# 5_POWER.net
KiCad netlist of a schematic drawn in Altium Designer
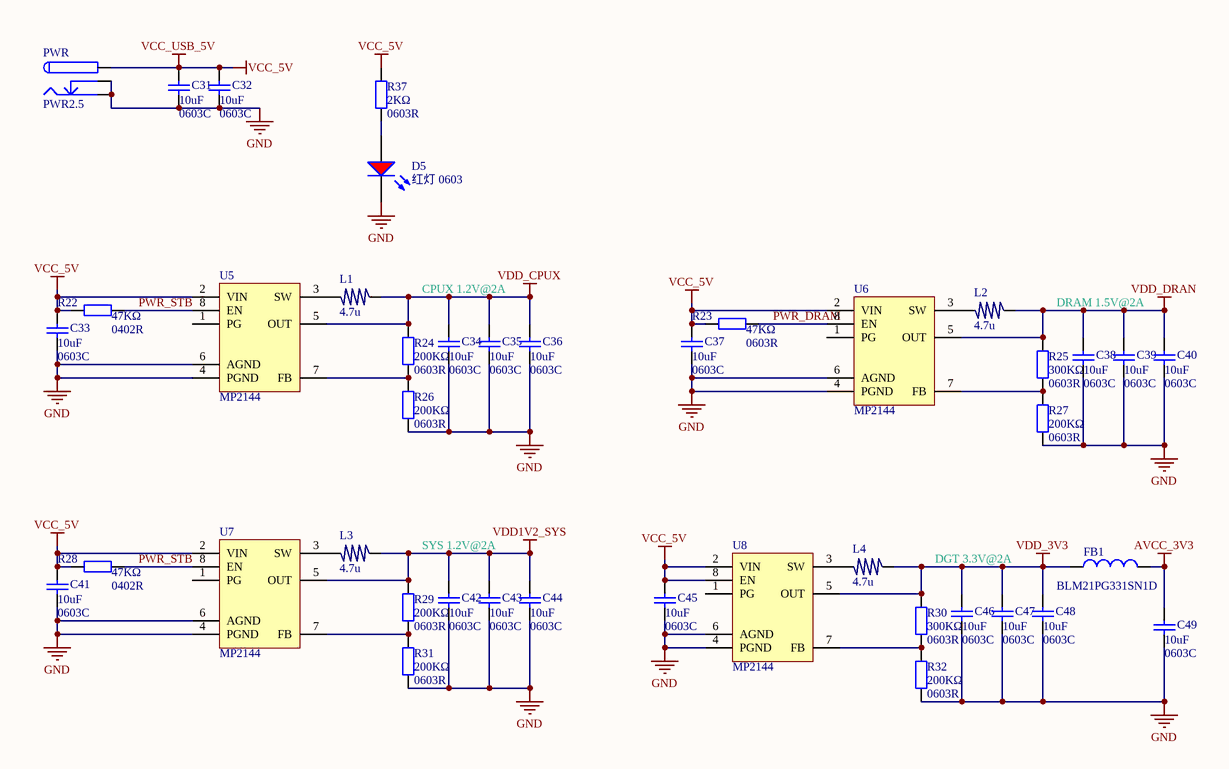
[diagram p0: 5_POWER.SchDoc]

(export (version "E")
  (design (tool "Eeschema 10.0.6"))
  (components
    (comp (ref "C31")
      (value "10uF")
      (footprint "0603_C")
      (description "贴片电容")
      (fields (field (name "PACKAGE") "0603C"))
      (libsource (lib "Miscellaneous Devices LC") (part "0603 1uF (105) 10% 50V"))
    )
    (comp (ref "C32")
      (value "10uF")
      (footprint "0603_C")
      (description "贴片电容")
      (fields (field (name "PACKAGE") "0603C"))
      (libsource (lib "Miscellaneous Devices LC") (part "0603 1uF (105) 10% 50V"))
    )
    (comp (ref "C33")
      (value "10uF")
      (footprint "0603_C")
      (description "贴片电容")
      (fields (field (name "PACKAGE") "0603C"))
      (libsource (lib "Miscellaneous Devices LC") (part "0603 1uF (105) 10% 50V"))
    )
    (comp (ref "C34")
      (value "10uF")
      (footprint "0603_C")
      (description "贴片电容")
      (fields (field (name "PACKAGE") "0603C"))
      (libsource (lib "Miscellaneous Devices LC") (part "0603 1uF (105) 10% 50V"))
    )
    (comp (ref "C35")
      (value "10uF")
      (footprint "0603_C")
      (description "贴片电容")
      (fields (field (name "PACKAGE") "0603C"))
      (libsource (lib "Miscellaneous Devices LC") (part "0603 1uF (105) 10% 50V"))
    )
    (comp (ref "C36")
      (value "10uF")
      (footprint "0603_C")
      (description "贴片电容")
      (fields (field (name "PACKAGE") "0603C"))
      (libsource (lib "Miscellaneous Devices LC") (part "0603 1uF (105) 10% 50V"))
    )
    (comp (ref "C37")
      (value "10uF")
      (footprint "0603_C")
      (description "贴片电容")
      (fields (field (name "PACKAGE") "0603C"))
      (libsource (lib "Miscellaneous Devices LC") (part "0603 1uF (105) 10% 50V"))
    )
    (comp (ref "C38")
      (value "10uF")
      (footprint "0603_C")
      (description "贴片电容")
      (fields (field (name "PACKAGE") "0603C"))
      (libsource (lib "Miscellaneous Devices LC") (part "0603 1uF (105) 10% 50V"))
    )
    (comp (ref "C39")
      (value "10uF")
      (footprint "0603_C")
      (description "贴片电容")
      (fields (field (name "PACKAGE") "0603C"))
      (libsource (lib "Miscellaneous Devices LC") (part "0603 1uF (105) 10% 50V"))
    )
    (comp (ref "C40")
      (value "10uF")
      (footprint "0603_C")
      (description "贴片电容")
      (fields (field (name "PACKAGE") "0603C"))
      (libsource (lib "Miscellaneous Devices LC") (part "0603 1uF (105) 10% 50V"))
    )
    (comp (ref "C41")
      (value "10uF")
      (footprint "0603_C")
      (description "贴片电容")
      (fields (field (name "PACKAGE") "0603C"))
      (libsource (lib "Miscellaneous Devices LC") (part "0603 1uF (105) 10% 50V"))
    )
    (comp (ref "C42")
      (value "10uF")
      (footprint "0603_C")
      (description "贴片电容")
      (fields (field (name "PACKAGE") "0603C"))
      (libsource (lib "Miscellaneous Devices LC") (part "0603 1uF (105) 10% 50V"))
    )
    (comp (ref "C43")
      (value "10uF")
      (footprint "0603_C")
      (description "贴片电容")
      (fields (field (name "PACKAGE") "0603C"))
      (libsource (lib "Miscellaneous Devices LC") (part "0603 1uF (105) 10% 50V"))
    )
    (comp (ref "C44")
      (value "10uF")
      (footprint "0603_C")
      (description "贴片电容")
      (fields (field (name "PACKAGE") "0603C"))
      (libsource (lib "Miscellaneous Devices LC") (part "0603 1uF (105) 10% 50V"))
    )
    (comp (ref "C45")
      (value "10uF")
      (footprint "0603_C")
      (description "贴片电容")
      (fields (field (name "PACKAGE") "0603C"))
      (libsource (lib "Miscellaneous Devices LC") (part "0603 1uF (105) 10% 50V"))
    )
    (comp (ref "C46")
      (value "10uF")
      (footprint "0603_C")
      (description "贴片电容")
      (fields (field (name "PACKAGE") "0603C"))
      (libsource (lib "Miscellaneous Devices LC") (part "0603 1uF (105) 10% 50V"))
    )
    (comp (ref "C47")
      (value "10uF")
      (footprint "0603_C")
      (description "贴片电容")
      (fields (field (name "PACKAGE") "0603C"))
      (libsource (lib "Miscellaneous Devices LC") (part "0603 1uF (105) 10% 50V"))
    )
    (comp (ref "C48")
      (value "10uF")
      (footprint "0603_C")
      (description "贴片电容")
      (fields (field (name "PACKAGE") "0603C"))
      (libsource (lib "Miscellaneous Devices LC") (part "0603 1uF (105) 10% 50V"))
    )
    (comp (ref "C49")
      (value "10uF")
      (footprint "0603_C")
      (description "贴片电容")
      (fields (field (name "PACKAGE") "0603C"))
      (libsource (lib "Miscellaneous Devices LC") (part "0603 1uF (105) 10% 50V"))
    )
    (comp (ref "D5")
      (value "红灯 0603")
      (footprint "0603_LED_S1")
      (description "发光二极管")
      (libsource (lib "Miscellaneous Devices LC") (part "0603 红灯"))
    )
    (comp (ref "FB1")
      (value "BLM21PG331SN1D")
      (footprint "F0805")
      (description "磁珠")
      (libsource (lib "MAGNET_L") (part "FB"))
    )
    (comp (ref "L1")
      (value "4.7u")
      (footprint "CD43NP")
      (fields (field (name "Comment") "4R7_CD43"))
      (libsource (lib "MAGNET_L") (part "L"))
    )
    (comp (ref "L2")
      (value "4.7u")
      (footprint "CD43NP")
      (fields (field (name "Comment") "4R7_CD43"))
      (libsource (lib "MAGNET_L") (part "L"))
    )
    (comp (ref "L3")
      (value "4.7u")
      (footprint "CD43NP")
      (fields (field (name "Comment") "4R7_CD43"))
      (libsource (lib "MAGNET_L") (part "L"))
    )
    (comp (ref "L4")
      (value "4.7u")
      (footprint "CD43NP")
      (fields (field (name "Comment") "4R7_CD43"))
      (libsource (lib "MAGNET_L") (part "L"))
    )
    (comp (ref "PWR")
      (value "PWR2.5")
      (footprint "DC-PJ044A")
      (description "Low Voltage Power Supply Connector")
      (fields (field (name "PUBLISHER") "Altium Limited"))
      (libsource (lib "MAGNET_L") (part "PWR2.5"))
    )
    (comp (ref "R22")
      (value "47KΩ")
      (footprint "0402_R")
      (description "贴片电阻")
      (fields (field (name "PACKAGE") "0402R"))
      (libsource (lib "") (part "0402 1KΩ (1001) 1%_1"))
    )
    (comp (ref "R23")
      (value "47KΩ")
      (footprint "0603_R")
      (description "贴片电阻")
      (fields (field (name "PACKAGE") "0603R"))
      (libsource (lib "") (part "0402 1KΩ (1001) 1%_1"))
    )
    (comp (ref "R24")
      (value "200KΩ")
      (footprint "0603_R")
      (description "贴片电阻")
      (fields (field (name "PACKAGE") "0603R"))
      (libsource (lib "Miscellaneous Devices LC") (part "0402 1KΩ (1001) 1%"))
    )
    (comp (ref "R25")
      (value "300KΩ")
      (footprint "0603_R")
      (description "贴片电阻")
      (fields (field (name "PACKAGE") "0603R"))
      (libsource (lib "Miscellaneous Devices LC") (part "0402 1KΩ (1001) 1%"))
    )
    (comp (ref "R26")
      (value "200KΩ")
      (footprint "0603_R")
      (description "贴片电阻")
      (fields (field (name "PACKAGE") "0603R"))
      (libsource (lib "Miscellaneous Devices LC") (part "0402 1KΩ (1001) 1%"))
    )
    (comp (ref "R27")
      (value "200KΩ")
      (footprint "0603_R")
      (description "贴片电阻")
      (fields (field (name "PACKAGE") "0603R"))
      (libsource (lib "Miscellaneous Devices LC") (part "0402 1KΩ (1001) 1%"))
    )
    (comp (ref "R28")
      (value "47KΩ")
      (footprint "0402_R")
      (description "贴片电阻")
      (fields (field (name "PACKAGE") "0402R"))
      (libsource (lib "") (part "0402 1KΩ (1001) 1%_1"))
    )
    (comp (ref "R29")
      (value "200KΩ")
      (footprint "0603_R")
      (description "贴片电阻")
      (fields (field (name "PACKAGE") "0603R"))
      (libsource (lib "Miscellaneous Devices LC") (part "0402 1KΩ (1001) 1%"))
    )
    (comp (ref "R30")
      (value "300KΩ")
      (footprint "0603_R")
      (description "贴片电阻")
      (fields (field (name "PACKAGE") "0603R"))
      (libsource (lib "Miscellaneous Devices LC") (part "0402 1KΩ (1001) 1%"))
    )
    (comp (ref "R31")
      (value "200KΩ")
      (footprint "0603_R")
      (description "贴片电阻")
      (fields (field (name "PACKAGE") "0603R"))
      (libsource (lib "Miscellaneous Devices LC") (part "0402 1KΩ (1001) 1%"))
    )
    (comp (ref "R32")
      (value "200KΩ")
      (footprint "0603_R")
      (description "贴片电阻")
      (fields (field (name "PACKAGE") "0603R"))
      (libsource (lib "Miscellaneous Devices LC") (part "0402 1KΩ (1001) 1%"))
    )
    (comp (ref "R37")
      (value "2KΩ")
      (footprint "0603_R")
      (description "贴片电阻")
      (fields (field (name "PACKAGE") "0603R"))
      (libsource (lib "Miscellaneous Devices LC") (part "0402 1KΩ (1001) 1%"))
    )
    (comp (ref "U5") (value "MP2144") (footprint "SOT23-8") (libsource (lib "MAGNET_L") (part "MP2144")))
    (comp (ref "U6") (value "MP2144") (footprint "SOT23-8") (libsource (lib "MAGNET_L") (part "MP2144")))
    (comp (ref "U7") (value "MP2144") (footprint "SOT23-8") (libsource (lib "MAGNET_L") (part "MP2144")))
    (comp (ref "U8") (value "MP2144") (footprint "SOT23-8") (libsource (lib "MAGNET_L") (part "MP2144")))
  )
  (nets
    (net (code "1") (name "/PWR_DRAM") (class "Default")
      (node (ref "R23") (pin "2") (pinfunction "2_2") (pintype "passive"))
      (node (ref "U6") (pin "8") (pinfunction "EN_8") (pintype "passive"))
    )
    (net (code "2") (name "/PWR_STB") (class "Default")
      (node (ref "R22") (pin "2") (pinfunction "2_2") (pintype "passive"))
      (node (ref "R28") (pin "2") (pinfunction "2_2") (pintype "passive"))
      (node (ref "U5") (pin "8") (pinfunction "EN_8") (pintype "passive"))
      (node (ref "U7") (pin "8") (pinfunction "EN_8") (pintype "passive"))
    )
    (net (code "3") (name "AVCC_3V3") (class "Default")
      (node (ref "C49") (pin "2") (pinfunction "2_2") (pintype "passive"))
      (node (ref "FB1") (pin "2") (pinfunction "2_2") (pintype "passive"))
    )
    (net (code "4") (name "GND") (class "Default")
      (node (ref "C31") (pin "1") (pinfunction "1_1") (pintype "passive"))
      (node (ref "C32") (pin "1") (pinfunction "1_1") (pintype "passive"))
      (node (ref "C33") (pin "1") (pinfunction "1_1") (pintype "passive"))
      (node (ref "C34") (pin "1") (pinfunction "1_1") (pintype "passive"))
      (node (ref "C35") (pin "1") (pinfunction "1_1") (pintype "passive"))
      (node (ref "C36") (pin "1") (pinfunction "1_1") (pintype "passive"))
      (node (ref "C37") (pin "1") (pinfunction "1_1") (pintype "passive"))
      (node (ref "C38") (pin "1") (pinfunction "1_1") (pintype "passive"))
      (node (ref "C39") (pin "1") (pinfunction "1_1") (pintype "passive"))
      (node (ref "C40") (pin "1") (pinfunction "1_1") (pintype "passive"))
      (node (ref "C41") (pin "1") (pinfunction "1_1") (pintype "passive"))
      (node (ref "C42") (pin "1") (pinfunction "1_1") (pintype "passive"))
      (node (ref "C43") (pin "1") (pinfunction "1_1") (pintype "passive"))
      (node (ref "C44") (pin "1") (pinfunction "1_1") (pintype "passive"))
      (node (ref "C45") (pin "1") (pinfunction "1_1") (pintype "passive"))
      (node (ref "C46") (pin "1") (pinfunction "1_1") (pintype "passive"))
      (node (ref "C47") (pin "1") (pinfunction "1_1") (pintype "passive"))
      (node (ref "C48") (pin "1") (pinfunction "1_1") (pintype "passive"))
      (node (ref "C49") (pin "1") (pinfunction "1_1") (pintype "passive"))
      (node (ref "D5") (pin "K") (pinfunction "K_K") (pintype "passive"))
      (node (ref "PWR") (pin "2") (pinfunction "2_2") (pintype "passive"))
      (node (ref "PWR") (pin "3") (pinfunction "3_3") (pintype "passive"))
      (node (ref "R26") (pin "2") (pinfunction "2_2") (pintype "passive"))
      (node (ref "R27") (pin "2") (pinfunction "2_2") (pintype "passive"))
      (node (ref "R31") (pin "2") (pinfunction "2_2") (pintype "passive"))
      (node (ref "R32") (pin "2") (pinfunction "2_2") (pintype "passive"))
      (node (ref "U5") (pin "4") (pinfunction "PGND_4") (pintype "passive"))
      (node (ref "U5") (pin "6") (pinfunction "AGND_6") (pintype "passive"))
      (node (ref "U6") (pin "4") (pinfunction "PGND_4") (pintype "passive"))
      (node (ref "U6") (pin "6") (pinfunction "AGND_6") (pintype "passive"))
      (node (ref "U7") (pin "4") (pinfunction "PGND_4") (pintype "passive"))
      (node (ref "U7") (pin "6") (pinfunction "AGND_6") (pintype "passive"))
      (node (ref "U8") (pin "4") (pinfunction "PGND_4") (pintype "passive"))
      (node (ref "U8") (pin "6") (pinfunction "AGND_6") (pintype "passive"))
    )
    (net (code "5") (name "Net-(D5-PadA)") (class "Default")
      (node (ref "D5") (pin "A") (pinfunction "A_A") (pintype "passive"))
      (node (ref "R37") (pin "2") (pinfunction "2_2") (pintype "passive"))
    )
    (net (code "6") (name "Net-(U5-FB)") (class "Default")
      (node (ref "R24") (pin "2") (pinfunction "2_2") (pintype "passive"))
      (node (ref "R26") (pin "1") (pinfunction "1_1") (pintype "passive"))
      (node (ref "U5") (pin "7") (pinfunction "FB_7") (pintype "passive"))
    )
    (net (code "7") (name "Net-(U5-SW)") (class "Default")
      (node (ref "L1") (pin "2") (pintype "passive"))
      (node (ref "U5") (pin "3") (pinfunction "SW_3") (pintype "passive"))
    )
    (net (code "8") (name "Net-(U6-FB)") (class "Default")
      (node (ref "R25") (pin "2") (pinfunction "2_2") (pintype "passive"))
      (node (ref "R27") (pin "1") (pinfunction "1_1") (pintype "passive"))
      (node (ref "U6") (pin "7") (pinfunction "FB_7") (pintype "passive"))
    )
    (net (code "9") (name "Net-(U6-SW)") (class "Default")
      (node (ref "L2") (pin "2") (pintype "passive"))
      (node (ref "U6") (pin "3") (pinfunction "SW_3") (pintype "passive"))
    )
    (net (code "10") (name "Net-(U7-FB)") (class "Default")
      (node (ref "R29") (pin "2") (pinfunction "2_2") (pintype "passive"))
      (node (ref "R31") (pin "1") (pinfunction "1_1") (pintype "passive"))
      (node (ref "U7") (pin "7") (pinfunction "FB_7") (pintype "passive"))
    )
    (net (code "11") (name "Net-(U7-SW)") (class "Default")
      (node (ref "L3") (pin "2") (pintype "passive"))
      (node (ref "U7") (pin "3") (pinfunction "SW_3") (pintype "passive"))
    )
    (net (code "12") (name "Net-(U8-FB)") (class "Default")
      (node (ref "R30") (pin "2") (pinfunction "2_2") (pintype "passive"))
      (node (ref "R32") (pin "1") (pinfunction "1_1") (pintype "passive"))
      (node (ref "U8") (pin "7") (pinfunction "FB_7") (pintype "passive"))
    )
    (net (code "13") (name "Net-(U8-SW)") (class "Default")
      (node (ref "L4") (pin "2") (pintype "passive"))
      (node (ref "U8") (pin "3") (pinfunction "SW_3") (pintype "passive"))
    )
    (net (code "14") (name "VCC_5V") (class "Default")
      (node (ref "C31") (pin "2") (pinfunction "2_2") (pintype "passive"))
      (node (ref "C32") (pin "2") (pinfunction "2_2") (pintype "passive"))
      (node (ref "C33") (pin "2") (pinfunction "2_2") (pintype "passive"))
      (node (ref "C37") (pin "2") (pinfunction "2_2") (pintype "passive"))
      (node (ref "C41") (pin "2") (pinfunction "2_2") (pintype "passive"))
      (node (ref "C45") (pin "2") (pinfunction "2_2") (pintype "passive"))
      (node (ref "PWR") (pin "1") (pinfunction "1_1") (pintype "passive"))
      (node (ref "R22") (pin "1") (pinfunction "1_1") (pintype "passive"))
      (node (ref "R23") (pin "1") (pinfunction "1_1") (pintype "passive"))
      (node (ref "R28") (pin "1") (pinfunction "1_1") (pintype "passive"))
      (node (ref "R37") (pin "1") (pinfunction "1_1") (pintype "passive"))
      (node (ref "U5") (pin "2") (pinfunction "VIN_2") (pintype "passive"))
      (node (ref "U6") (pin "2") (pinfunction "VIN_2") (pintype "passive"))
      (node (ref "U7") (pin "2") (pinfunction "VIN_2") (pintype "passive"))
      (node (ref "U8") (pin "2") (pinfunction "VIN_2") (pintype "passive"))
      (node (ref "U8") (pin "8") (pinfunction "EN_8") (pintype "passive"))
    )
    (net (code "15") (name "VDD1V2_SYS") (class "Default")
      (node (ref "C42") (pin "2") (pinfunction "2_2") (pintype "passive"))
      (node (ref "C43") (pin "2") (pinfunction "2_2") (pintype "passive"))
      (node (ref "C44") (pin "2") (pinfunction "2_2") (pintype "passive"))
      (node (ref "L3") (pin "1") (pintype "passive"))
      (node (ref "R29") (pin "1") (pinfunction "1_1") (pintype "passive"))
      (node (ref "U7") (pin "5") (pinfunction "OUT_5") (pintype "passive"))
    )
    (net (code "16") (name "VDD_3V3") (class "Default")
      (node (ref "C46") (pin "2") (pinfunction "2_2") (pintype "passive"))
      (node (ref "C47") (pin "2") (pinfunction "2_2") (pintype "passive"))
      (node (ref "C48") (pin "2") (pinfunction "2_2") (pintype "passive"))
      (node (ref "FB1") (pin "1") (pinfunction "1_1") (pintype "passive"))
      (node (ref "L4") (pin "1") (pintype "passive"))
      (node (ref "R30") (pin "1") (pinfunction "1_1") (pintype "passive"))
      (node (ref "U8") (pin "5") (pinfunction "OUT_5") (pintype "passive"))
    )
    (net (code "17") (name "VDD_CPUX") (class "Default")
      (node (ref "C34") (pin "2") (pinfunction "2_2") (pintype "passive"))
      (node (ref "C35") (pin "2") (pinfunction "2_2") (pintype "passive"))
      (node (ref "C36") (pin "2") (pinfunction "2_2") (pintype "passive"))
      (node (ref "L1") (pin "1") (pintype "passive"))
      (node (ref "R24") (pin "1") (pinfunction "1_1") (pintype "passive"))
      (node (ref "U5") (pin "5") (pinfunction "OUT_5") (pintype "passive"))
    )
    (net (code "18") (name "VDD_DRAN") (class "Default")
      (node (ref "C38") (pin "2") (pinfunction "2_2") (pintype "passive"))
      (node (ref "C39") (pin "2") (pinfunction "2_2") (pintype "passive"))
      (node (ref "C40") (pin "2") (pinfunction "2_2") (pintype "passive"))
      (node (ref "L2") (pin "1") (pintype "passive"))
      (node (ref "R25") (pin "1") (pinfunction "1_1") (pintype "passive"))
      (node (ref "U6") (pin "5") (pinfunction "OUT_5") (pintype "passive"))
    )
    (net (code "19") (name "unconnected-(U5-PG-Pad1)") (class "Default")
      (node (ref "U5") (pin "1") (pinfunction "PG_1") (pintype "passive"))
    )
    (net (code "20") (name "unconnected-(U6-PG-Pad1)") (class "Default")
      (node (ref "U6") (pin "1") (pinfunction "PG_1") (pintype "passive"))
    )
    (net (code "21") (name "unconnected-(U7-PG-Pad1)") (class "Default")
      (node (ref "U7") (pin "1") (pinfunction "PG_1") (pintype "passive"))
    )
    (net (code "22") (name "unconnected-(U8-PG-Pad1)") (class "Default")
      (node (ref "U8") (pin "1") (pinfunction "PG_1") (pintype "passive"))
    )
  )
)
